# Sheet1.net
KiCad netlist of a schematic drawn in Altium Designer
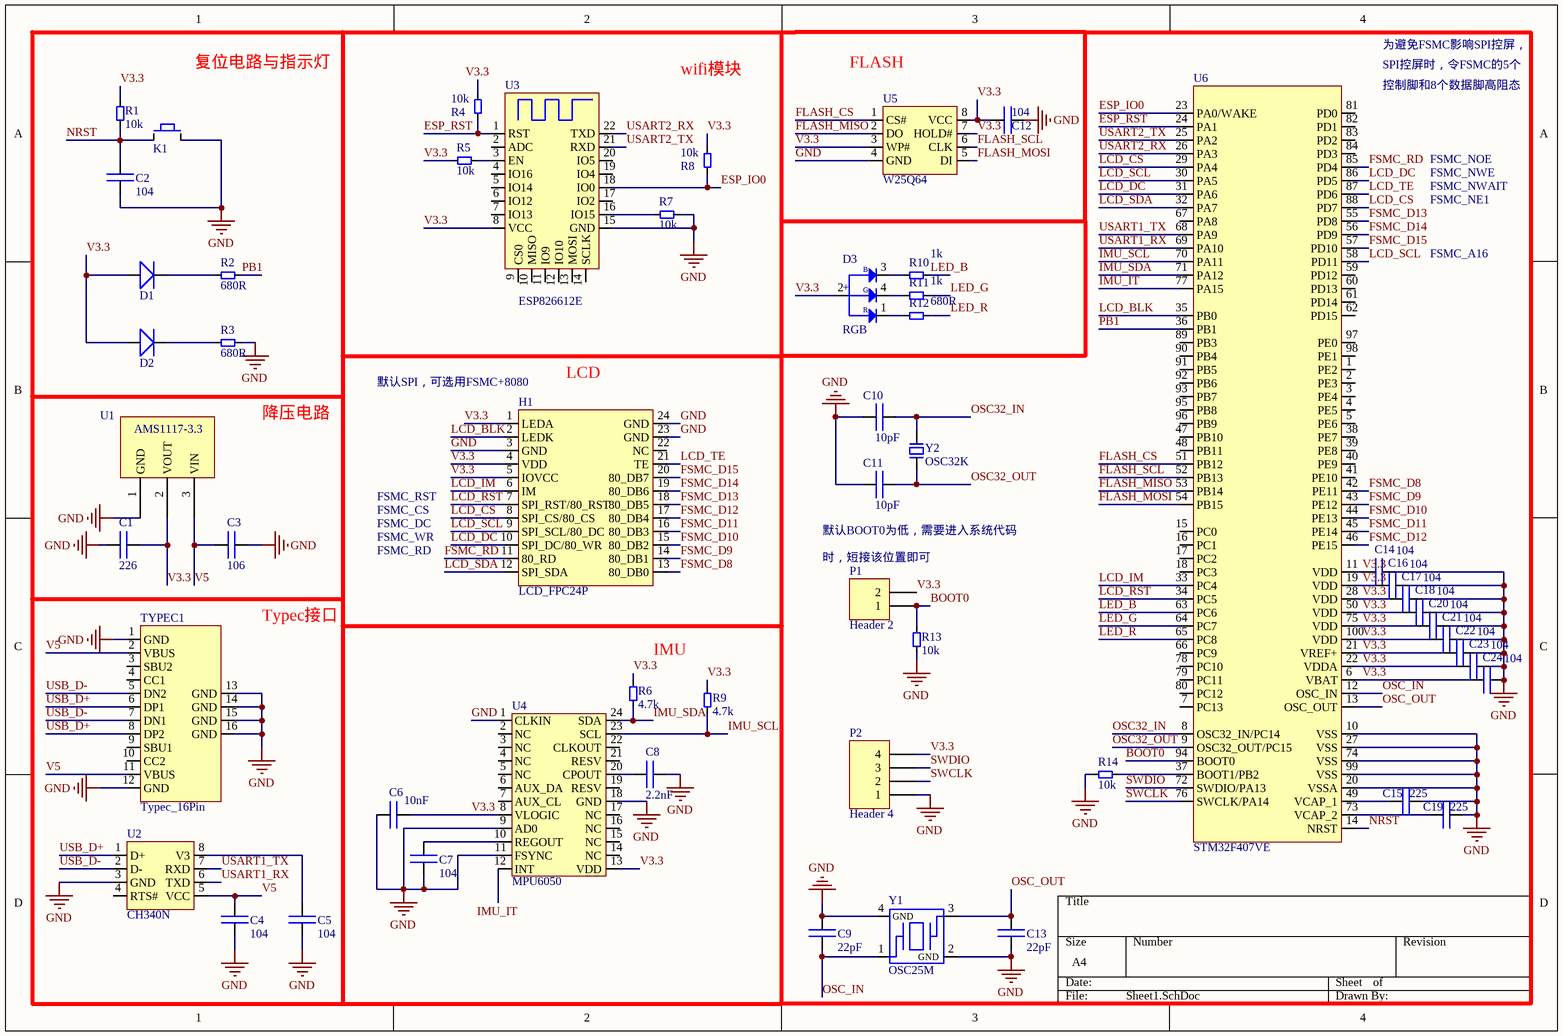
[diagram p0: Sheet1.SchDoc]

(export (version "E")
  (design (tool "Eeschema 10.0.6"))
  (components
    (comp (ref "C1")
      (value "226")
      (footprint "0805C")
      (description "电容")
      (libsource (lib "Schlib2") (part "CAP"))
    )
    (comp (ref "C2")
      (value "104")
      (footprint "0805C")
      (description "电容")
      (libsource (lib "Schlib1") (part "CAP"))
    )
    (comp (ref "C3")
      (value "106")
      (footprint "0805C")
      (description "电容")
      (libsource (lib "Schlib2") (part "CAP"))
    )
    (comp (ref "C4")
      (value "104")
      (footprint "0805C")
      (description "电容")
      (libsource (lib "Schlib2") (part "CAP"))
    )
    (comp (ref "C5")
      (value "104")
      (footprint "0805C")
      (description "电容")
      (libsource (lib "Schlib2") (part "CAP"))
    )
    (comp (ref "C6")
      (value "10nF")
      (footprint "0805C")
      (description "电容")
      (libsource (lib "Schlib2") (part "CAP"))
    )
    (comp (ref "C7")
      (value "104")
      (footprint "0805C")
      (description "电容")
      (libsource (lib "Schlib2") (part "CAP"))
    )
    (comp (ref "C8")
      (value "2.2nF")
      (footprint "0805C")
      (description "电容")
      (libsource (lib "Schlib2") (part "CAP"))
    )
    (comp (ref "C9")
      (value "22pF")
      (footprint "0805C")
      (description "电容")
      (libsource (lib "Schlib2") (part "CAP"))
    )
    (comp (ref "C10")
      (value "10pF")
      (footprint "0805C")
      (description "电容")
      (libsource (lib "Schlib2") (part "CAP"))
    )
    (comp (ref "C11")
      (value "10pF")
      (footprint "0805C")
      (description "电容")
      (libsource (lib "Schlib2") (part "CAP"))
    )
    (comp (ref "C12")
      (value "104")
      (footprint "0805C")
      (description "电容")
      (libsource (lib "Schlib2") (part "CAP"))
    )
    (comp (ref "C13")
      (value "22pF")
      (footprint "0805C")
      (description "电容")
      (libsource (lib "Schlib2") (part "CAP"))
    )
    (comp (ref "C14")
      (value "104")
      (footprint "0805C")
      (description "电容")
      (libsource (lib "Schlib2") (part "CAP"))
    )
    (comp (ref "C15")
      (value "225")
      (footprint "0805C")
      (description "电容")
      (libsource (lib "Schlib2") (part "CAP"))
    )
    (comp (ref "C16")
      (value "104")
      (footprint "0805C")
      (description "电容")
      (libsource (lib "Schlib2") (part "CAP"))
    )
    (comp (ref "C17")
      (value "104")
      (footprint "0805C")
      (description "电容")
      (libsource (lib "Schlib2") (part "CAP"))
    )
    (comp (ref "C18")
      (value "104")
      (footprint "0805C")
      (description "电容")
      (libsource (lib "Schlib2") (part "CAP"))
    )
    (comp (ref "C19")
      (value "225")
      (footprint "0805C")
      (description "电容")
      (libsource (lib "Schlib2") (part "CAP"))
    )
    (comp (ref "C20")
      (value "104")
      (footprint "0805C")
      (description "电容")
      (libsource (lib "Schlib2") (part "CAP"))
    )
    (comp (ref "C21")
      (value "104")
      (footprint "0805C")
      (description "电容")
      (libsource (lib "Schlib2") (part "CAP"))
    )
    (comp (ref "C22")
      (value "104")
      (footprint "0805C")
      (description "电容")
      (libsource (lib "Schlib2") (part "CAP"))
    )
    (comp (ref "C23")
      (value "104")
      (footprint "0805C")
      (description "电容")
      (libsource (lib "Schlib2") (part "CAP"))
    )
    (comp (ref "C24")
      (value "104")
      (footprint "0805C")
      (description "电容")
      (libsource (lib "Schlib2") (part "CAP"))
    )
    (comp (ref "D1")
      (value "LED")
      (footprint "0805D")
      (description "LED灯")
      (libsource (lib "Schlib1") (part "LED"))
    )
    (comp (ref "D2")
      (value "LED")
      (footprint "0805D")
      (description "LED灯")
      (libsource (lib "Schlib1") (part "LED"))
    )
    (comp (ref "D3") (value "RGB") (footprint "RGB") (libsource (lib "Schlib1") (part "RGB")))
    (comp (ref "H1") (value "LCD_FPC24P") (footprint "FPC24") (libsource (lib "Schlib1") (part "LCD_FPC24P")))
    (comp (ref "K1")
      (value "KEY")
      (footprint "Key3x6x2.5")
      (description "按键")
      (libsource (lib "Schlib1") (part "KEY"))
    )
    (comp (ref "P1")
      (value "Header 2")
      (footprint "HDR1X2")
      (description "Header, 2-Pin")
      (fields (field (name "PUBLISHER") "Altium Limited"))
      (libsource (lib "Miscellaneous Connectors") (part "Header 2"))
    )
    (comp (ref "P2")
      (value "Header 4")
      (footprint "HDR1X4")
      (description "Header, 4-Pin")
      (fields (field (name "PUBLISHER") "Altium Limited"))
      (libsource (lib "Miscellaneous Connectors") (part "Header 4"))
    )
    (comp (ref "R1")
      (value "10k")
      (footprint "0805R")
      (description "电阻")
      (libsource (lib "Schlib2") (part "RES"))
    )
    (comp (ref "R2")
      (value "680R")
      (footprint "0805R")
      (description "电阻")
      (libsource (lib "Schlib2") (part "RES"))
    )
    (comp (ref "R3")
      (value "680R")
      (footprint "0805R")
      (description "电阻")
      (libsource (lib "Schlib2") (part "RES"))
    )
    (comp (ref "R4")
      (value "10k")
      (footprint "0805R")
      (description "电阻")
      (libsource (lib "Schlib2") (part "RES"))
    )
    (comp (ref "R5")
      (value "10k")
      (footprint "0805R")
      (description "电阻")
      (libsource (lib "Schlib2") (part "RES"))
    )
    (comp (ref "R6")
      (value "4.7k")
      (footprint "0805R")
      (description "电阻")
      (libsource (lib "Schlib2") (part "RES"))
    )
    (comp (ref "R7")
      (value "10k")
      (footprint "0805R")
      (description "电阻")
      (libsource (lib "Schlib2") (part "RES"))
    )
    (comp (ref "R8")
      (value "10k")
      (footprint "0805R")
      (description "电阻")
      (libsource (lib "Schlib2") (part "RES"))
    )
    (comp (ref "R9")
      (value "4.7k")
      (footprint "0805R")
      (description "电阻")
      (libsource (lib "Schlib2") (part "RES"))
    )
    (comp (ref "R10")
      (value "1k")
      (footprint "0805R")
      (description "电阻")
      (libsource (lib "Schlib2") (part "RES"))
    )
    (comp (ref "R11")
      (value "1k")
      (footprint "0805R")
      (description "电阻")
      (libsource (lib "Schlib2") (part "RES"))
    )
    (comp (ref "R12")
      (value "680R")
      (footprint "0805R")
      (description "电阻")
      (libsource (lib "Schlib2") (part "RES"))
    )
    (comp (ref "R13")
      (value "10k")
      (footprint "0805R")
      (description "电阻")
      (libsource (lib "Schlib2") (part "RES"))
    )
    (comp (ref "R14")
      (value "10k")
      (footprint "0805R")
      (description "电阻")
      (libsource (lib "Schlib2") (part "RES"))
    )
    (comp (ref "TYPEC1")
      (value "Typec_16Pin")
      (footprint "Typec_16Pin")
      (libsource (lib "Schlib1") (part "Typec_16Pin"))
    )
    (comp (ref "U1")
      (value "AMS1117-3.3")
      (footprint "SOT-89")
      (description "IC")
      (libsource (lib "Schlib2") (part "AMS1117-3.3"))
    )
    (comp (ref "U2") (value "CH340N") (footprint "CH340N") (libsource (lib "Schlib1") (part "CH340N")))
    (comp (ref "U3")
      (value "ESP826612E")
      (footprint "ESP826612E")
      (libsource (lib "Schlib1") (part "ESP826612E"))
    )
    (comp (ref "U4") (value "MPU6050") (footprint "MPU6050") (libsource (lib "Schlib1") (part "MPU6050")))
    (comp (ref "U5") (value "W25Q64") (footprint "W25Q64") (libsource (lib "Schlib1") (part "W25Q64")))
    (comp (ref "U6")
      (value "STM32F407VE")
      (footprint "STM32F407VET6")
      (libsource (lib "Schlib1") (part "STM32F407VET6"))
    )
    (comp (ref "Y1") (value "OSC25M") (footprint "OSC25M") (libsource (lib "Schlib1") (part "OSC25M")))
    (comp (ref "Y2") (value "OSC32K") (footprint "OSC32K") (libsource (lib "Schlib1") (part "OSC32K")))
  )
  (nets
    (net (code "1") (name "/BOOT0") (class "Default")
      (node (ref "P1") (pin "1") (pinfunction "1_1") (pintype "passive"))
      (node (ref "R13") (pin "2") (pinfunction "2_2") (pintype "passive"))
      (node (ref "U6") (pin "94") (pinfunction "BOOT0_94") (pintype "passive"))
    )
    (net (code "2") (name "/ESP_IO0") (class "Default")
      (node (ref "R8") (pin "1") (pinfunction "1_1") (pintype "passive"))
      (node (ref "U3") (pin "18") (pinfunction "IO0_18") (pintype "passive"))
      (node (ref "U6") (pin "23") (pinfunction "PA0/WAKE_23") (pintype "passive"))
    )
    (net (code "3") (name "/ESP_RST") (class "Default")
      (node (ref "R4") (pin "1") (pinfunction "1_1") (pintype "passive"))
      (node (ref "U3") (pin "1") (pinfunction "RST_1") (pintype "passive"))
      (node (ref "U6") (pin "24") (pinfunction "PA1_24") (pintype "passive"))
    )
    (net (code "4") (name "/FLASH_CS") (class "Default")
      (node (ref "U5") (pin "1") (pinfunction "CS#_1") (pintype "passive"))
      (node (ref "U6") (pin "51") (pinfunction "PB12_51") (pintype "passive"))
    )
    (net (code "5") (name "/FLASH_MISO") (class "Default")
      (node (ref "U5") (pin "2") (pinfunction "DO_2") (pintype "passive"))
      (node (ref "U6") (pin "53") (pinfunction "PB14_53") (pintype "passive"))
    )
    (net (code "6") (name "/FLASH_MOSI") (class "Default")
      (node (ref "U5") (pin "5") (pinfunction "DI_5") (pintype "passive"))
      (node (ref "U6") (pin "54") (pinfunction "PB15_54") (pintype "passive"))
    )
    (net (code "7") (name "/FLASH_SCL") (class "Default")
      (node (ref "U5") (pin "6") (pinfunction "CLK_6") (pintype "passive"))
      (node (ref "U6") (pin "52") (pinfunction "PB13_52") (pintype "passive"))
    )
    (net (code "8") (name "/FSMC_D8") (class "Default")
      (node (ref "H1") (pin "13") (pinfunction "80_DB0_13") (pintype "passive"))
      (node (ref "U6") (pin "42") (pinfunction "PE11_42") (pintype "passive"))
    )
    (net (code "9") (name "/FSMC_D9") (class "Default")
      (node (ref "H1") (pin "14") (pinfunction "80_DB1_14") (pintype "passive"))
      (node (ref "U6") (pin "43") (pinfunction "PE12_43") (pintype "passive"))
    )
    (net (code "10") (name "/FSMC_D10") (class "Default")
      (node (ref "H1") (pin "15") (pinfunction "80_DB2_15") (pintype "passive"))
      (node (ref "U6") (pin "44") (pinfunction "PE13_44") (pintype "passive"))
    )
    (net (code "11") (name "/FSMC_D11") (class "Default")
      (node (ref "H1") (pin "16") (pinfunction "80_DB3_16") (pintype "passive"))
      (node (ref "U6") (pin "45") (pinfunction "PE14_45") (pintype "passive"))
    )
    (net (code "12") (name "/FSMC_D12") (class "Default")
      (node (ref "H1") (pin "17") (pinfunction "80_DB4_17") (pintype "passive"))
      (node (ref "U6") (pin "46") (pinfunction "PE15_46") (pintype "passive"))
    )
    (net (code "13") (name "/FSMC_D13") (class "Default")
      (node (ref "H1") (pin "18") (pinfunction "80_DB5_18") (pintype "passive"))
      (node (ref "U6") (pin "55") (pinfunction "PD8_55") (pintype "passive"))
    )
    (net (code "14") (name "/FSMC_D14") (class "Default")
      (node (ref "H1") (pin "19") (pinfunction "80_DB6_19") (pintype "passive"))
      (node (ref "U6") (pin "56") (pinfunction "PD9_56") (pintype "passive"))
    )
    (net (code "15") (name "/FSMC_D15") (class "Default")
      (node (ref "H1") (pin "20") (pinfunction "80_DB7_20") (pintype "passive"))
      (node (ref "U6") (pin "57") (pinfunction "PD10_57") (pintype "passive"))
    )
    (net (code "16") (name "/FSMC_RD") (class "Default")
      (node (ref "H1") (pin "11") (pinfunction "80_RD_11") (pintype "passive"))
      (node (ref "U6") (pin "85") (pinfunction "PD4_85") (pintype "passive"))
    )
    (net (code "17") (name "/IMU_IT") (class "Default")
      (node (ref "U4") (pin "12") (pinfunction "INT_12") (pintype "passive"))
      (node (ref "U6") (pin "77") (pinfunction "PA15_77") (pintype "passive"))
    )
    (net (code "18") (name "/IMU_SCL") (class "Default")
      (node (ref "R9") (pin "1") (pinfunction "1_1") (pintype "passive"))
      (node (ref "U4") (pin "23") (pinfunction "SCL_23") (pintype "passive"))
      (node (ref "U6") (pin "70") (pinfunction "PA11_70") (pintype "passive"))
    )
    (net (code "19") (name "/IMU_SDA") (class "Default")
      (node (ref "R6") (pin "1") (pinfunction "1_1") (pintype "passive"))
      (node (ref "U4") (pin "24") (pinfunction "SDA_24") (pintype "passive"))
      (node (ref "U6") (pin "71") (pinfunction "PA12_71") (pintype "passive"))
    )
    (net (code "20") (name "/LCD_BLK") (class "Default")
      (node (ref "H1") (pin "2") (pinfunction "LEDK_2") (pintype "passive"))
      (node (ref "U6") (pin "35") (pinfunction "PB0_35") (pintype "passive"))
    )
    (net (code "21") (name "/LCD_CS") (class "Default")
      (node (ref "H1") (pin "8") (pinfunction "SPI_CS/80_CS_8") (pintype "passive"))
      (node (ref "U6") (pin "29") (pinfunction "PA4_29") (pintype "passive"))
      (node (ref "U6") (pin "88") (pinfunction "PD7_88") (pintype "passive"))
    )
    (net (code "22") (name "/LCD_DC") (class "Default")
      (node (ref "H1") (pin "10") (pinfunction "SPI_DC/80_WR_10") (pintype "passive"))
      (node (ref "U6") (pin "31") (pinfunction "PA6_31") (pintype "passive"))
      (node (ref "U6") (pin "86") (pinfunction "PD5_86") (pintype "passive"))
    )
    (net (code "23") (name "/LCD_IM") (class "Default")
      (node (ref "H1") (pin "6") (pinfunction "IM_6") (pintype "passive"))
      (node (ref "U6") (pin "33") (pinfunction "PC4_33") (pintype "passive"))
    )
    (net (code "24") (name "/LCD_RST") (class "Default")
      (node (ref "H1") (pin "7") (pinfunction "SPI_RST/80_RST_7") (pintype "passive"))
      (node (ref "U6") (pin "34") (pinfunction "PC5_34") (pintype "passive"))
    )
    (net (code "25") (name "/LCD_SCL") (class "Default")
      (node (ref "H1") (pin "9") (pinfunction "SPI_SCL/80_DC_9") (pintype "passive"))
      (node (ref "U6") (pin "30") (pinfunction "PA5_30") (pintype "passive"))
      (node (ref "U6") (pin "58") (pinfunction "PD11_58") (pintype "passive"))
    )
    (net (code "26") (name "/LCD_SDA") (class "Default")
      (node (ref "H1") (pin "12") (pinfunction "SPI_SDA_12") (pintype "passive"))
      (node (ref "U6") (pin "32") (pinfunction "PA7_32") (pintype "passive"))
    )
    (net (code "27") (name "/LCD_TE") (class "Default")
      (node (ref "H1") (pin "21") (pinfunction "TE_21") (pintype "passive"))
      (node (ref "U6") (pin "87") (pinfunction "PD6_87") (pintype "passive"))
    )
    (net (code "28") (name "/LED_B") (class "Default")
      (node (ref "R10") (pin "1") (pinfunction "1_1") (pintype "passive"))
      (node (ref "U6") (pin "63") (pinfunction "PC6_63") (pintype "passive"))
    )
    (net (code "29") (name "/LED_G") (class "Default")
      (node (ref "R11") (pin "1") (pinfunction "1_1") (pintype "passive"))
      (node (ref "U6") (pin "64") (pinfunction "PC7_64") (pintype "passive"))
    )
    (net (code "30") (name "/LED_R") (class "Default")
      (node (ref "R12") (pin "1") (pinfunction "1_1") (pintype "passive"))
      (node (ref "U6") (pin "65") (pinfunction "PC8_65") (pintype "passive"))
    )
    (net (code "31") (name "/NRST") (class "Default")
      (node (ref "C2") (pin "2") (pinfunction "2_2") (pintype "passive"))
      (node (ref "K1") (pin "1") (pinfunction "1_1") (pintype "passive"))
      (node (ref "R1") (pin "1") (pinfunction "1_1") (pintype "passive"))
      (node (ref "U6") (pin "14") (pinfunction "NRST_14") (pintype "passive"))
    )
    (net (code "32") (name "/OSC32_IN") (class "Default")
      (node (ref "C10") (pin "2") (pinfunction "2_2") (pintype "passive"))
      (node (ref "U6") (pin "8") (pinfunction "OSC32_IN/PC14_8") (pintype "passive"))
      (node (ref "Y2") (pin "2") (pintype "passive"))
    )
    (net (code "33") (name "/OSC32_OUT") (class "Default")
      (node (ref "C11") (pin "2") (pinfunction "2_2") (pintype "passive"))
      (node (ref "U6") (pin "9") (pinfunction "OSC32_OUT/PC15_9") (pintype "passive"))
      (node (ref "Y2") (pin "1") (pintype "passive"))
    )
    (net (code "34") (name "/OSC_IN") (class "Default")
      (node (ref "C9") (pin "2") (pinfunction "2_2") (pintype "passive"))
      (node (ref "U6") (pin "12") (pinfunction "OSC_IN_12") (pintype "passive"))
      (node (ref "Y1") (pin "1") (pintype "passive"))
    )
    (net (code "35") (name "/OSC_OUT") (class "Default")
      (node (ref "C13") (pin "1") (pinfunction "1_1") (pintype "passive"))
      (node (ref "U6") (pin "13") (pinfunction "OSC_OUT_13") (pintype "passive"))
      (node (ref "Y1") (pin "3") (pintype "passive"))
    )
    (net (code "36") (name "/PB1") (class "Default")
      (node (ref "R2") (pin "1") (pinfunction "1_1") (pintype "passive"))
      (node (ref "U6") (pin "36") (pinfunction "PB1_36") (pintype "passive"))
    )
    (net (code "37") (name "/SWCLK") (class "Default")
      (node (ref "P2") (pin "2") (pinfunction "2_2") (pintype "passive"))
      (node (ref "U6") (pin "76") (pinfunction "SWCLK/PA14_76") (pintype "passive"))
    )
    (net (code "38") (name "/SWDIO") (class "Default")
      (node (ref "P2") (pin "3") (pinfunction "3_3") (pintype "passive"))
      (node (ref "U6") (pin "72") (pinfunction "SWDIO/PA13_72") (pintype "passive"))
    )
    (net (code "39") (name "/USART1_RX") (class "Default")
      (node (ref "U2") (pin "6") (pinfunction "TXD_6") (pintype "passive"))
      (node (ref "U6") (pin "69") (pinfunction "PA10_69") (pintype "passive"))
    )
    (net (code "40") (name "/USART1_TX") (class "Default")
      (node (ref "U2") (pin "7") (pinfunction "RXD_7") (pintype "passive"))
      (node (ref "U6") (pin "68") (pinfunction "PA9_68") (pintype "passive"))
    )
    (net (code "41") (name "/USART2_RX") (class "Default")
      (node (ref "U3") (pin "22") (pinfunction "TXD_22") (pintype "passive"))
      (node (ref "U6") (pin "26") (pinfunction "PA3_26") (pintype "passive"))
    )
    (net (code "42") (name "/USART2_TX") (class "Default")
      (node (ref "U3") (pin "21") (pinfunction "RXD_21") (pintype "passive"))
      (node (ref "U6") (pin "25") (pinfunction "PA2_25") (pintype "passive"))
    )
    (net (code "43") (name "/USB_D+") (class "Default")
      (node (ref "TYPEC1") (pin "6") (pinfunction "DP1_6") (pintype "passive"))
      (node (ref "TYPEC1") (pin "8") (pinfunction "DP2_8") (pintype "passive"))
      (node (ref "U2") (pin "1") (pinfunction "D+_1") (pintype "passive"))
    )
    (net (code "44") (name "/USB_D-") (class "Default")
      (node (ref "TYPEC1") (pin "5") (pinfunction "DN2_5") (pintype "passive"))
      (node (ref "TYPEC1") (pin "7") (pinfunction "DN1_7") (pintype "passive"))
      (node (ref "U2") (pin "2") (pinfunction "D-_2") (pintype "passive"))
    )
    (net (code "45") (name "/V3.3") (class "Default")
      (node (ref "C1") (pin "1") (pinfunction "1_1") (pintype "passive"))
      (node (ref "C12") (pin "2") (pinfunction "2_2") (pintype "passive"))
      (node (ref "C14") (pin "2") (pinfunction "2_2") (pintype "passive"))
      (node (ref "C16") (pin "2") (pinfunction "2_2") (pintype "passive"))
      (node (ref "C17") (pin "2") (pinfunction "2_2") (pintype "passive"))
      (node (ref "C18") (pin "2") (pinfunction "2_2") (pintype "passive"))
      (node (ref "C20") (pin "2") (pinfunction "2_2") (pintype "passive"))
      (node (ref "C21") (pin "2") (pinfunction "2_2") (pintype "passive"))
      (node (ref "C22") (pin "2") (pinfunction "2_2") (pintype "passive"))
      (node (ref "C23") (pin "2") (pinfunction "2_2") (pintype "passive"))
      (node (ref "C24") (pin "2") (pinfunction "2_2") (pintype "passive"))
      (node (ref "C6") (pin "1") (pinfunction "1_1") (pintype "passive"))
      (node (ref "D1") (pin "2") (pinfunction "2_2") (pintype "passive"))
      (node (ref "D2") (pin "2") (pinfunction "2_2") (pintype "passive"))
      (node (ref "D3") (pin "2") (pintype "passive"))
      (node (ref "H1") (pin "1") (pinfunction "LEDA_1") (pintype "passive"))
      (node (ref "H1") (pin "4") (pinfunction "VDD_4") (pintype "passive"))
      (node (ref "H1") (pin "5") (pinfunction "IOVCC_5") (pintype "passive"))
      (node (ref "P1") (pin "2") (pinfunction "2_2") (pintype "passive"))
      (node (ref "P2") (pin "4") (pinfunction "4_4") (pintype "passive"))
      (node (ref "R1") (pin "2") (pinfunction "2_2") (pintype "passive"))
      (node (ref "R4") (pin "2") (pinfunction "2_2") (pintype "passive"))
      (node (ref "R5") (pin "2") (pinfunction "2_2") (pintype "passive"))
      (node (ref "R6") (pin "2") (pinfunction "2_2") (pintype "passive"))
      (node (ref "R8") (pin "2") (pinfunction "2_2") (pintype "passive"))
      (node (ref "R9") (pin "2") (pinfunction "2_2") (pintype "passive"))
      (node (ref "U1") (pin "2") (pinfunction "VOUT_2") (pintype "passive"))
      (node (ref "U3") (pin "8") (pinfunction "VCC_8") (pintype "passive"))
      (node (ref "U4") (pin "13") (pinfunction "VDD_13") (pintype "passive"))
      (node (ref "U4") (pin "8") (pinfunction "VLOGIC_8") (pintype "passive"))
      (node (ref "U5") (pin "3") (pinfunction "WP#_3") (pintype "passive"))
      (node (ref "U5") (pin "7") (pinfunction "HOLD#_7") (pintype "passive"))
      (node (ref "U5") (pin "8") (pinfunction "VCC_8") (pintype "passive"))
      (node (ref "U6") (pin "100") (pinfunction "VDD_100") (pintype "passive"))
      (node (ref "U6") (pin "11") (pinfunction "VDD_11") (pintype "passive"))
      (node (ref "U6") (pin "19") (pinfunction "VDD_19") (pintype "passive"))
      (node (ref "U6") (pin "21") (pinfunction "VREF+_21") (pintype "passive"))
      (node (ref "U6") (pin "22") (pinfunction "VDDA_22") (pintype "passive"))
      (node (ref "U6") (pin "28") (pinfunction "VDD_28") (pintype "passive"))
      (node (ref "U6") (pin "50") (pinfunction "VDD_50") (pintype "passive"))
      (node (ref "U6") (pin "6") (pinfunction "VBAT_6") (pintype "passive"))
      (node (ref "U6") (pin "75") (pinfunction "VDD_75") (pintype "passive"))
    )
    (net (code "46") (name "/V5") (class "Default")
      (node (ref "C3") (pin "2") (pinfunction "2_2") (pintype "passive"))
      (node (ref "C4") (pin "2") (pinfunction "2_2") (pintype "passive"))
      (node (ref "TYPEC1") (pin "11") (pinfunction "VBUS_11") (pintype "passive"))
      (node (ref "TYPEC1") (pin "2") (pinfunction "VBUS_2") (pintype "passive"))
      (node (ref "U1") (pin "3") (pinfunction "VIN_3") (pintype "passive"))
      (node (ref "U2") (pin "5") (pinfunction "VCC_5") (pintype "passive"))
    )
    (net (code "47") (name "GND") (class "Default")
      (node (ref "C1") (pin "2") (pinfunction "2_2") (pintype "passive"))
      (node (ref "C10") (pin "1") (pinfunction "1_1") (pintype "passive"))
      (node (ref "C11") (pin "1") (pinfunction "1_1") (pintype "passive"))
      (node (ref "C12") (pin "1") (pinfunction "1_1") (pintype "passive"))
      (node (ref "C13") (pin "2") (pinfunction "2_2") (pintype "passive"))
      (node (ref "C14") (pin "1") (pinfunction "1_1") (pintype "passive"))
      (node (ref "C15") (pin "1") (pinfunction "1_1") (pintype "passive"))
      (node (ref "C16") (pin "1") (pinfunction "1_1") (pintype "passive"))
      (node (ref "C17") (pin "1") (pinfunction "1_1") (pintype "passive"))
      (node (ref "C18") (pin "1") (pinfunction "1_1") (pintype "passive"))
      (node (ref "C19") (pin "1") (pinfunction "1_1") (pintype "passive"))
      (node (ref "C2") (pin "1") (pinfunction "1_1") (pintype "passive"))
      (node (ref "C20") (pin "1") (pinfunction "1_1") (pintype "passive"))
      (node (ref "C21") (pin "1") (pinfunction "1_1") (pintype "passive"))
      (node (ref "C22") (pin "1") (pinfunction "1_1") (pintype "passive"))
      (node (ref "C23") (pin "1") (pinfunction "1_1") (pintype "passive"))
      (node (ref "C24") (pin "1") (pinfunction "1_1") (pintype "passive"))
      (node (ref "C3") (pin "1") (pinfunction "1_1") (pintype "passive"))
      (node (ref "C4") (pin "1") (pinfunction "1_1") (pintype "passive"))
      (node (ref "C5") (pin "1") (pinfunction "1_1") (pintype "passive"))
      (node (ref "C6") (pin "2") (pinfunction "2_2") (pintype "passive"))
      (node (ref "C7") (pin "2") (pinfunction "2_2") (pintype "passive"))
      (node (ref "C8") (pin "2") (pinfunction "2_2") (pintype "passive"))
      (node (ref "C9") (pin "1") (pinfunction "1_1") (pintype "passive"))
      (node (ref "H1") (pin "23") (pinfunction "GND_23") (pintype "passive"))
      (node (ref "H1") (pin "24") (pinfunction "GND_24") (pintype "passive"))
      (node (ref "H1") (pin "3") (pinfunction "GND_3") (pintype "passive"))
      (node (ref "K1") (pin "2") (pinfunction "2_2") (pintype "passive"))
      (node (ref "P2") (pin "1") (pinfunction "1_1") (pintype "passive"))
      (node (ref "R13") (pin "1") (pinfunction "1_1") (pintype "passive"))
      (node (ref "R14") (pin "1") (pinfunction "1_1") (pintype "passive"))
      (node (ref "R3") (pin "1") (pinfunction "1_1") (pintype "passive"))
      (node (ref "R7") (pin "1") (pinfunction "1_1") (pintype "passive"))
      (node (ref "TYPEC1") (pin "1") (pinfunction "GND_1") (pintype "passive"))
      (node (ref "TYPEC1") (pin "12") (pinfunction "GND_12") (pintype "passive"))
      (node (ref "TYPEC1") (pin "13") (pinfunction "GND_13") (pintype "passive"))
      (node (ref "TYPEC1") (pin "14") (pinfunction "GND_14") (pintype "passive"))
      (node (ref "TYPEC1") (pin "15") (pinfunction "GND_15") (pintype "passive"))
      (node (ref "TYPEC1") (pin "16") (pinfunction "GND_16") (pintype "passive"))
      (node (ref "U1") (pin "1") (pinfunction "GND_1") (pintype "passive"))
      (node (ref "U2") (pin "3") (pinfunction "GND_3") (pintype "passive"))
      (node (ref "U3") (pin "15") (pinfunction "GND_15") (pintype "passive"))
      (node (ref "U4") (pin "1") (pinfunction "CLKIN_1") (pintype "passive"))
      (node (ref "U4") (pin "11") (pinfunction "FSYNC_11") (pintype "passive"))
      (node (ref "U4") (pin "18") (pinfunction "GND_18") (pintype "passive"))
      (node (ref "U4") (pin "9") (pinfunction "AD0_9") (pintype "passive"))
      (node (ref "U5") (pin "4") (pinfunction "GND_4") (pintype "passive"))
      (node (ref "U6") (pin "10") (pinfunction "VSS_10") (pintype "passive"))
      (node (ref "U6") (pin "20") (pinfunction "VSSA_20") (pintype "passive"))
      (node (ref "U6") (pin "27") (pinfunction "VSS_27") (pintype "passive"))
      (node (ref "U6") (pin "74") (pinfunction "VSS_74") (pintype "passive"))
      (node (ref "U6") (pin "99") (pinfunction "VSS_99") (pintype "passive"))
      (node (ref "Y1") (pin "2") (pinfunction "GND_2") (pintype "passive"))
      (node (ref "Y1") (pin "4") (pinfunction "GND_4") (pintype "passive"))
    )
    (net (code "48") (name "Net-(D1-Pad1)") (class "Default")
      (node (ref "D1") (pin "1") (pinfunction "1_1") (pintype "passive"))
      (node (ref "R2") (pin "2") (pinfunction "2_2") (pintype "passive"))
    )
    (net (code "49") (name "Net-(D2-Pad1)") (class "Default")
      (node (ref "D2") (pin "1") (pinfunction "1_1") (pintype "passive"))
      (node (ref "R3") (pin "2") (pinfunction "2_2") (pintype "passive"))
    )
    (net (code "50") (name "Net-(D3-Pad1)") (class "Default")
      (node (ref "D3") (pin "1") (pintype "passive"))
      (node (ref "R12") (pin "2") (pinfunction "2_2") (pintype "passive"))
    )
    (net (code "51") (name "Net-(D3-Pad3)") (class "Default")
      (node (ref "D3") (pin "3") (pintype "passive"))
      (node (ref "R10") (pin "2") (pinfunction "2_2") (pintype "passive"))
    )
    (net (code "52") (name "Net-(D3-Pad4)") (class "Default")
      (node (ref "D3") (pin "4") (pintype "passive"))
      (node (ref "R11") (pin "2") (pinfunction "2_2") (pintype "passive"))
    )
    (net (code "53") (name "Net-(U2-V3)") (class "Default")
      (node (ref "C5") (pin "2") (pinfunction "2_2") (pintype "passive"))
      (node (ref "U2") (pin "8") (pinfunction "V3_8") (pintype "passive"))
    )
    (net (code "54") (name "Net-(U3-EN)") (class "Default")
      (node (ref "R5") (pin "1") (pinfunction "1_1") (pintype "passive"))
      (node (ref "U3") (pin "3") (pinfunction "EN_3") (pintype "passive"))
    )
    (net (code "55") (name "Net-(U3-IO15)") (class "Default")
      (node (ref "R7") (pin "2") (pinfunction "2_2") (pintype "passive"))
      (node (ref "U3") (pin "16") (pinfunction "IO15_16") (pintype "passive"))
    )
    (net (code "56") (name "Net-(U4-CPOUT)") (class "Default")
      (node (ref "C8") (pin "1") (pinfunction "1_1") (pintype "passive"))
      (node (ref "U4") (pin "20") (pinfunction "CPOUT_20") (pintype "passive"))
    )
    (net (code "57") (name "Net-(U4-REGOUT)") (class "Default")
      (node (ref "C7") (pin "1") (pinfunction "1_1") (pintype "passive"))
      (node (ref "U4") (pin "10") (pinfunction "REGOUT_10") (pintype "passive"))
    )
    (net (code "58") (name "Net-(U6-BOOT1{slash}PB2)") (class "Default")
      (node (ref "R14") (pin "2") (pinfunction "2_2") (pintype "passive"))
      (node (ref "U6") (pin "37") (pinfunction "BOOT1/PB2_37") (pintype "passive"))
    )
    (net (code "59") (name "Net-(U6-VCAP_1)") (class "Default")
      (node (ref "C15") (pin "2") (pinfunction "2_2") (pintype "passive"))
      (node (ref "U6") (pin "49") (pinfunction "VCAP_1_49") (pintype "passive"))
    )
    (net (code "60") (name "Net-(U6-VCAP_2)") (class "Default")
      (node (ref "C19") (pin "2") (pinfunction "2_2") (pintype "passive"))
      (node (ref "U6") (pin "73") (pinfunction "VCAP_2_73") (pintype "passive"))
    )
    (net (code "61") (name "unconnected-(H1-NC-Pad22)") (class "Default")
      (node (ref "H1") (pin "22") (pinfunction "NC_22") (pintype "passive"))
    )
    (net (code "62") (name "unconnected-(TYPEC1-CC1-Pad4)") (class "Default")
      (node (ref "TYPEC1") (pin "4") (pinfunction "CC1_4") (pintype "passive"))
    )
    (net (code "63") (name "unconnected-(TYPEC1-CC2-Pad10)") (class "Default")
      (node (ref "TYPEC1") (pin "10") (pinfunction "CC2_10") (pintype "passive"))
    )
    (net (code "64") (name "unconnected-(TYPEC1-SBU1-Pad9)") (class "Default")
      (node (ref "TYPEC1") (pin "9") (pinfunction "SBU1_9") (pintype "passive"))
    )
    (net (code "65") (name "unconnected-(TYPEC1-SBU2-Pad3)") (class "Default")
      (node (ref "TYPEC1") (pin "3") (pinfunction "SBU2_3") (pintype "passive"))
    )
    (net (code "66") (name "unconnected-(U2-RTS#-Pad4)") (class "Default")
      (node (ref "U2") (pin "4") (pinfunction "RTS#_4") (pintype "passive"))
    )
    (net (code "67") (name "unconnected-(U3-ADC-Pad2)") (class "Default")
      (node (ref "U3") (pin "2") (pinfunction "ADC_2") (pintype "passive"))
    )
    (net (code "68") (name "unconnected-(U3-CS0-Pad9)") (class "Default")
      (node (ref "U3") (pin "9") (pinfunction "CS0_9") (pintype "passive"))
    )
    (net (code "69") (name "unconnected-(U3-IO2-Pad17)") (class "Default")
      (node (ref "U3") (pin "17") (pinfunction "IO2_17") (pintype "passive"))
    )
    (net (code "70") (name "unconnected-(U3-IO4-Pad19)") (class "Default")
      (node (ref "U3") (pin "19") (pinfunction "IO4_19") (pintype "passive"))
    )
    (net (code "71") (name "unconnected-(U3-IO5-Pad20)") (class "Default")
      (node (ref "U3") (pin "20") (pinfunction "IO5_20") (pintype "passive"))
    )
    (net (code "72") (name "unconnected-(U3-IO9-Pad11)") (class "Default")
      (node (ref "U3") (pin "11") (pinfunction "IO9_11") (pintype "passive"))
    )
    (net (code "73") (name "unconnected-(U3-IO10-Pad12)") (class "Default")
      (node (ref "U3") (pin "12") (pinfunction "IO10_12") (pintype "passive"))
    )
    (net (code "74") (name "unconnected-(U3-IO12-Pad6)") (class "Default")
      (node (ref "U3") (pin "6") (pinfunction "IO12_6") (pintype "passive"))
    )
    (net (code "75") (name "unconnected-(U3-IO13-Pad7)") (class "Default")
      (node (ref "U3") (pin "7") (pinfunction "IO13_7") (pintype "passive"))
    )
    (net (code "76") (name "unconnected-(U3-IO14-Pad5)") (class "Default")
      (node (ref "U3") (pin "5") (pinfunction "IO14_5") (pintype "passive"))
    )
    (net (code "77") (name "unconnected-(U3-IO16-Pad4)") (class "Default")
      (node (ref "U3") (pin "4") (pinfunction "IO16_4") (pintype "passive"))
    )
    (net (code "78") (name "unconnected-(U3-MISO-Pad10)") (class "Default")
      (node (ref "U3") (pin "10") (pinfunction "MISO_10") (pintype "passive"))
    )
    (net (code "79") (name "unconnected-(U3-MOSI-Pad13)") (class "Default")
      (node (ref "U3") (pin "13") (pinfunction "MOSI_13") (pintype "passive"))
    )
    (net (code "80") (name "unconnected-(U3-SCLK-Pad14)") (class "Default")
      (node (ref "U3") (pin "14") (pinfunction "SCLK_14") (pintype "passive"))
    )
    (net (code "81") (name "unconnected-(U4-AUX_CL-Pad7)") (class "Default")
      (node (ref "U4") (pin "7") (pinfunction "AUX_CL_7") (pintype "passive"))
    )
    (net (code "82") (name "unconnected-(U4-AUX_DA-Pad6)") (class "Default")
      (node (ref "U4") (pin "6") (pinfunction "AUX_DA_6") (pintype "passive"))
    )
    (net (code "83") (name "unconnected-(U4-CLKOUT-Pad22)") (class "Default")
      (node (ref "U4") (pin "22") (pinfunction "CLKOUT_22") (pintype "passive"))
    )
    (net (code "84") (name "unconnected-(U4-NC-Pad2)") (class "Default")
      (node (ref "U4") (pin "2") (pinfunction "NC_2") (pintype "passive"))
    )
    (net (code "85") (name "unconnected-(U4-NC-Pad3)") (class "Default")
      (node (ref "U4") (pin "3") (pinfunction "NC_3") (pintype "passive"))
    )
    (net (code "86") (name "unconnected-(U4-NC-Pad4)") (class "Default")
      (node (ref "U4") (pin "4") (pinfunction "NC_4") (pintype "passive"))
    )
    (net (code "87") (name "unconnected-(U4-NC-Pad5)") (class "Default")
      (node (ref "U4") (pin "5") (pinfunction "NC_5") (pintype "passive"))
    )
    (net (code "88") (name "unconnected-(U4-NC-Pad14)") (class "Default")
      (node (ref "U4") (pin "14") (pinfunction "NC_14") (pintype "passive"))
    )
    (net (code "89") (name "unconnected-(U4-NC-Pad15)") (class "Default")
      (node (ref "U4") (pin "15") (pinfunction "NC_15") (pintype "passive"))
    )
    (net (code "90") (name "unconnected-(U4-NC-Pad16)") (class "Default")
      (node (ref "U4") (pin "16") (pinfunction "NC_16") (pintype "passive"))
    )
    (net (code "91") (name "unconnected-(U4-NC-Pad17)") (class "Default")
      (node (ref "U4") (pin "17") (pinfunction "NC_17") (pintype "passive"))
    )
    (net (code "92") (name "unconnected-(U4-RESV-Pad19)") (class "Default")
      (node (ref "U4") (pin "19") (pinfunction "RESV_19") (pintype "passive"))
    )
    (net (code "93") (name "unconnected-(U4-RESV-Pad21)") (class "Default")
      (node (ref "U4") (pin "21") (pinfunction "RESV_21") (pintype "passive"))
    )
    (net (code "94") (name "unconnected-(U6-PA8-Pad67)") (class "Default")
      (node (ref "U6") (pin "67") (pinfunction "PA8_67") (pintype "passive"))
    )
    (net (code "95") (name "unconnected-(U6-PB3-Pad89)") (class "Default")
      (node (ref "U6") (pin "89") (pinfunction "PB3_89") (pintype "passive"))
    )
    (net (code "96") (name "unconnected-(U6-PB4-Pad90)") (class "Default")
      (node (ref "U6") (pin "90") (pinfunction "PB4_90") (pintype "passive"))
    )
    (net (code "97") (name "unconnected-(U6-PB5-Pad91)") (class "Default")
      (node (ref "U6") (pin "91") (pinfunction "PB5_91") (pintype "passive"))
    )
    (net (code "98") (name "unconnected-(U6-PB6-Pad92)") (class "Default")
      (node (ref "U6") (pin "92") (pinfunction "PB6_92") (pintype "passive"))
    )
    (net (code "99") (name "unconnected-(U6-PB7-Pad93)") (class "Default")
      (node (ref "U6") (pin "93") (pinfunction "PB7_93") (pintype "passive"))
    )
    (net (code "100") (name "unconnected-(U6-PB8-Pad95)") (class "Default")
      (node (ref "U6") (pin "95") (pinfunction "PB8_95") (pintype "passive"))
    )
    (net (code "101") (name "unconnected-(U6-PB9-Pad96)") (class "Default")
      (node (ref "U6") (pin "96") (pinfunction "PB9_96") (pintype "passive"))
    )
    (net (code "102") (name "unconnected-(U6-PB10-Pad47)") (class "Default")
      (node (ref "U6") (pin "47") (pinfunction "PB10_47") (pintype "passive"))
    )
    (net (code "103") (name "unconnected-(U6-PB11-Pad48)") (class "Default")
      (node (ref "U6") (pin "48") (pinfunction "PB11_48") (pintype "passive"))
    )
    (net (code "104") (name "unconnected-(U6-PC0-Pad15)") (class "Default")
      (node (ref "U6") (pin "15") (pinfunction "PC0_15") (pintype "passive"))
    )
    (net (code "105") (name "unconnected-(U6-PC1-Pad16)") (class "Default")
      (node (ref "U6") (pin "16") (pinfunction "PC1_16") (pintype "passive"))
    )
    (net (code "106") (name "unconnected-(U6-PC2-Pad17)") (class "Default")
      (node (ref "U6") (pin "17") (pinfunction "PC2_17") (pintype "passive"))
    )
    (net (code "107") (name "unconnected-(U6-PC3-Pad18)") (class "Default")
      (node (ref "U6") (pin "18") (pinfunction "PC3_18") (pintype "passive"))
    )
    (net (code "108") (name "unconnected-(U6-PC9-Pad66)") (class "Default")
      (node (ref "U6") (pin "66") (pinfunction "PC9_66") (pintype "passive"))
    )
    (net (code "109") (name "unconnected-(U6-PC10-Pad78)") (class "Default")
      (node (ref "U6") (pin "78") (pinfunction "PC10_78") (pintype "passive"))
    )
    (net (code "110") (name "unconnected-(U6-PC11-Pad79)") (class "Default")
      (node (ref "U6") (pin "79") (pinfunction "PC11_79") (pintype "passive"))
    )
    (net (code "111") (name "unconnected-(U6-PC12-Pad80)") (class "Default")
      (node (ref "U6") (pin "80") (pinfunction "PC12_80") (pintype "passive"))
    )
    (net (code "112") (name "unconnected-(U6-PC13-Pad7)") (class "Default")
      (node (ref "U6") (pin "7") (pinfunction "PC13_7") (pintype "passive"))
    )
    (net (code "113") (name "unconnected-(U6-PD0-Pad81)") (class "Default")
      (node (ref "U6") (pin "81") (pinfunction "PD0_81") (pintype "passive"))
    )
    (net (code "114") (name "unconnected-(U6-PD1-Pad82)") (class "Default")
      (node (ref "U6") (pin "82") (pinfunction "PD1_82") (pintype "passive"))
    )
    (net (code "115") (name "unconnected-(U6-PD2-Pad83)") (class "Default")
      (node (ref "U6") (pin "83") (pinfunction "PD2_83") (pintype "passive"))
    )
    (net (code "116") (name "unconnected-(U6-PD3-Pad84)") (class "Default")
      (node (ref "U6") (pin "84") (pinfunction "PD3_84") (pintype "passive"))
    )
    (net (code "117") (name "unconnected-(U6-PD12-Pad59)") (class "Default")
      (node (ref "U6") (pin "59") (pinfunction "PD12_59") (pintype "passive"))
    )
    (net (code "118") (name "unconnected-(U6-PD13-Pad60)") (class "Default")
      (node (ref "U6") (pin "60") (pinfunction "PD13_60") (pintype "passive"))
    )
    (net (code "119") (name "unconnected-(U6-PD14-Pad61)") (class "Default")
      (node (ref "U6") (pin "61") (pinfunction "PD14_61") (pintype "passive"))
    )
    (net (code "120") (name "unconnected-(U6-PD15-Pad62)") (class "Default")
      (node (ref "U6") (pin "62") (pinfunction "PD15_62") (pintype "passive"))
    )
    (net (code "121") (name "unconnected-(U6-PE0-Pad97)") (class "Default")
      (node (ref "U6") (pin "97") (pinfunction "PE0_97") (pintype "passive"))
    )
    (net (code "122") (name "unconnected-(U6-PE1-Pad98)") (class "Default")
      (node (ref "U6") (pin "98") (pinfunction "PE1_98") (pintype "passive"))
    )
    (net (code "123") (name "unconnected-(U6-PE2-Pad1)") (class "Default")
      (node (ref "U6") (pin "1") (pinfunction "PE2_1") (pintype "passive"))
    )
    (net (code "124") (name "unconnected-(U6-PE3-Pad2)") (class "Default")
      (node (ref "U6") (pin "2") (pinfunction "PE3_2") (pintype "passive"))
    )
    (net (code "125") (name "unconnected-(U6-PE4-Pad3)") (class "Default")
      (node (ref "U6") (pin "3") (pinfunction "PE4_3") (pintype "passive"))
    )
    (net (code "126") (name "unconnected-(U6-PE5-Pad4)") (class "Default")
      (node (ref "U6") (pin "4") (pinfunction "PE5_4") (pintype "passive"))
    )
    (net (code "127") (name "unconnected-(U6-PE6-Pad5)") (class "Default")
      (node (ref "U6") (pin "5") (pinfunction "PE6_5") (pintype "passive"))
    )
    (net (code "128") (name "unconnected-(U6-PE7-Pad38)") (class "Default")
      (node (ref "U6") (pin "38") (pinfunction "PE7_38") (pintype "passive"))
    )
    (net (code "129") (name "unconnected-(U6-PE8-Pad39)") (class "Default")
      (node (ref "U6") (pin "39") (pinfunction "PE8_39") (pintype "passive"))
    )
    (net (code "130") (name "unconnected-(U6-PE9-Pad40)") (class "Default")
      (node (ref "U6") (pin "40") (pinfunction "PE9_40") (pintype "passive"))
    )
    (net (code "131") (name "unconnected-(U6-PE10-Pad41)") (class "Default")
      (node (ref "U6") (pin "41") (pinfunction "PE10_41") (pintype "passive"))
    )
  )
)
